# -_-.net
KiCad netlist of a schematic drawn in Altium Designer
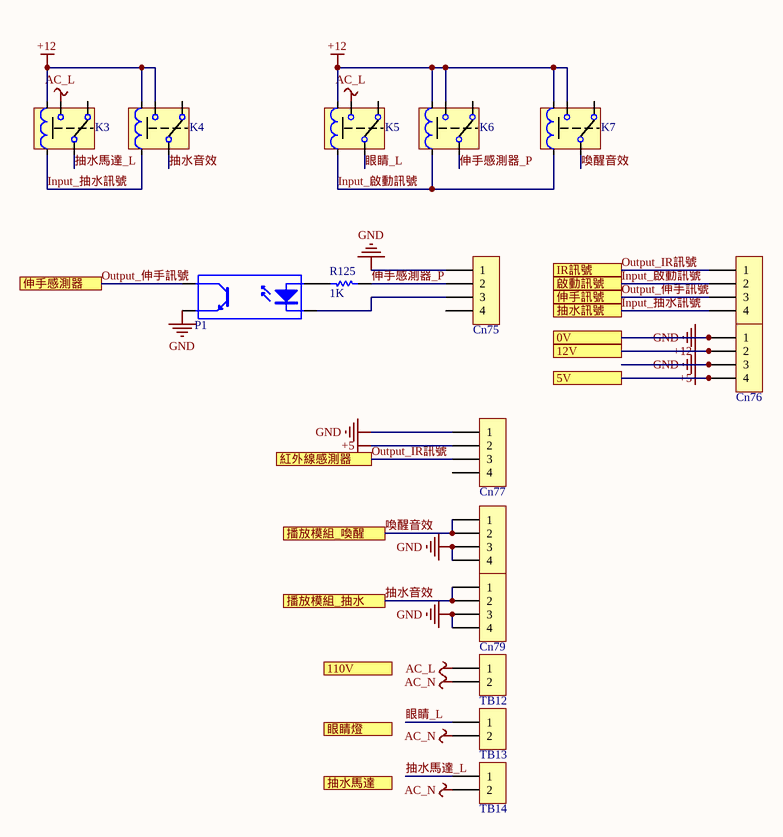
[diagram p0: 行天宮-流亡暗道-石像.SchDoc]

(export (version "E")
  (design (tool "Eeschema 10.0.6"))
  (components
    (comp (ref "Cn74")
      (value "KF2510-4")
      (footprint "Connector_KF2510-4W")
      (description "接線端子")
      (libsource (lib "MyLibray") (part "Contact(4P)"))
    )
    (comp (ref "Cn75")
      (value "KF2510-4")
      (footprint "Connector_KF2510-4W")
      (description "接線端子")
      (libsource (lib "MyLibray") (part "Contact(4P)"))
    )
    (comp (ref "Cn76")
      (value "KF2510-4")
      (footprint "Connector_KF2510-4W")
      (description "接線端子")
      (libsource (lib "MyLibray") (part "Contact(4P)"))
    )
    (comp (ref "Cn77")
      (value "KF2510-4")
      (footprint "Connector_KF2510-4W")
      (description "接線端子")
      (libsource (lib "MyLibray") (part "Contact(4P)"))
    )
    (comp (ref "Cn78")
      (value "KF2510-4")
      (footprint "Connector_KF2510-4W")
      (description "接線端子")
      (libsource (lib "MyLibray") (part "Contact(4P)"))
    )
    (comp (ref "Cn79")
      (value "KF2510-4")
      (footprint "Connector_KF2510-4W")
      (description "接線端子")
      (libsource (lib "MyLibray") (part "Contact(4P)"))
    )
    (comp (ref "K3")
      (value "G2R-1-24VDC")
      (footprint "RELAY-HF41F-012-ZST")
      (description "繼電器")
      (libsource (lib "MyLibray") (part "Relay"))
    )
    (comp (ref "K4")
      (value "G2R-1-24VDC")
      (footprint "RELAY-HF41F-012-ZST")
      (description "繼電器")
      (libsource (lib "MyLibray") (part "Relay"))
    )
    (comp (ref "K5")
      (value "G2R-1-24VDC")
      (footprint "RELAY-HF41F-012-ZST")
      (description "繼電器")
      (libsource (lib "MyLibray") (part "Relay"))
    )
    (comp (ref "K6")
      (value "G2R-1-24VDC")
      (footprint "RELAY-HF41F-012-ZST")
      (description "繼電器")
      (libsource (lib "MyLibray") (part "Relay"))
    )
    (comp (ref "K7")
      (value "G2R-1-24VDC")
      (footprint "RELAY-HF41F-012-ZST")
      (description "繼電器")
      (libsource (lib "MyLibray") (part "Relay"))
    )
    (comp (ref "P1")
      (value "PC817")
      (footprint "PC817")
      (description "光耦")
      (libsource (lib "MyLibray") (part "PC817"))
    )
    (comp (ref "R125")
      (value "1K")
      (footprint "Res_1/4")
      (description "電阻")
      (libsource (lib "MyLibray") (part "Res"))
    )
    (comp (ref "TB12")
      (value "ZB25(2P)")
      (footprint "Terminal block(KF2EDGR-5.08 _2P)")
      (description "端子台")
      (libsource (lib "MyLibray") (part "Terminal block(2P)"))
    )
    (comp (ref "TB13")
      (value "ZB25(2P)")
      (footprint "Terminal block(KF2EDGR-5.08 _2P)")
      (description "端子台")
      (libsource (lib "MyLibray") (part "Terminal block(2P)"))
    )
    (comp (ref "TB14")
      (value "ZB25(2P)")
      (footprint "Terminal block(KF2EDGR-5.08 _2P)")
      (description "端子台")
      (libsource (lib "MyLibray") (part "Terminal block(2P)"))
    )
  )
  (nets
    (net (code "1") (name "+5") (class "Default")
      (node (ref "Cn76") (pin "4") (pinfunction "4_4") (pintype "passive"))
      (node (ref "Cn77") (pin "2") (pinfunction "2_2") (pintype "passive"))
    )
    (net (code "2") (name "+12") (class "Default")
      (node (ref "Cn76") (pin "2") (pinfunction "2_2") (pintype "passive"))
      (node (ref "K3") (pin "5") (pinfunction "A2_5") (pintype "passive"))
      (node (ref "K4") (pin "2") (pinfunction "NO_2") (pintype "passive"))
      (node (ref "K4") (pin "5") (pinfunction "A2_5") (pintype "passive"))
      (node (ref "K5") (pin "5") (pinfunction "A2_5") (pintype "passive"))
      (node (ref "K6") (pin "2") (pinfunction "NO_2") (pintype "passive"))
      (node (ref "K6") (pin "5") (pinfunction "A2_5") (pintype "passive"))
      (node (ref "K7") (pin "2") (pinfunction "NO_2") (pintype "passive"))
      (node (ref "K7") (pin "5") (pinfunction "A2_5") (pintype "passive"))
    )
    (net (code "4") (name "/Input_啟動訊號") (class "Default")
      (node (ref "Cn74") (pin "2") (pinfunction "2_2") (pintype "passive"))
      (node (ref "K5") (pin "4") (pinfunction "A1_4") (pintype "passive"))
      (node (ref "K6") (pin "4") (pinfunction "A1_4") (pintype "passive"))
      (node (ref "K7") (pin "4") (pinfunction "A1_4") (pintype "passive"))
    )
    (net (code "5") (name "/Input_抽水訊號") (class "Default")
      (node (ref "Cn74") (pin "4") (pinfunction "4_4") (pintype "passive"))
      (node (ref "K3") (pin "4") (pinfunction "A1_4") (pintype "passive"))
      (node (ref "K4") (pin "4") (pinfunction "A1_4") (pintype "passive"))
    )
    (net (code "6") (name "/Output_IR訊號") (class "Default")
      (node (ref "Cn74") (pin "1") (pinfunction "1_1") (pintype "passive"))
      (node (ref "Cn77") (pin "3") (pinfunction "3_3") (pintype "passive"))
    )
    (net (code "7") (name "/Output_伸手訊號") (class "Default")
      (node (ref "Cn74") (pin "3") (pinfunction "3_3") (pintype "passive"))
      (node (ref "P1") (pin "4") (pinfunction "C_4") (pintype "passive"))
    )
    (net (code "8") (name "/伸手感測器_P") (class "Default")
      (node (ref "Cn75") (pin "2") (pinfunction "2_2") (pintype "passive"))
      (node (ref "K6") (pin "1") (pinfunction "COM_1") (pintype "passive"))
      (node (ref "R125") (pin "2") (pinfunction "2_2") (pintype "passive"))
    )
    (net (code "9") (name "/喚醒音效") (class "Default")
      (node (ref "Cn78") (pin "1") (pinfunction "1_1") (pintype "passive"))
      (node (ref "Cn78") (pin "2") (pinfunction "2_2") (pintype "passive"))
      (node (ref "K7") (pin "1") (pinfunction "COM_1") (pintype "passive"))
    )
    (net (code "10") (name "/抽水音效") (class "Default")
      (node (ref "Cn79") (pin "1") (pinfunction "1_1") (pintype "passive"))
      (node (ref "Cn79") (pin "2") (pinfunction "2_2") (pintype "passive"))
      (node (ref "K4") (pin "1") (pinfunction "COM_1") (pintype "passive"))
    )
    (net (code "12") (name "/抽水馬達_L") (class "Default")
      (node (ref "K3") (pin "1") (pinfunction "COM_1") (pintype "passive"))
      (node (ref "TB14") (pin "1") (pinfunction "1_1") (pintype "passive"))
    )
    (net (code "13") (name "/眼睛_L") (class "Default")
      (node (ref "K5") (pin "1") (pinfunction "COM_1") (pintype "passive"))
      (node (ref "TB13") (pin "1") (pinfunction "1_1") (pintype "passive"))
    )
    (net (code "15") (name "AC_L") (class "Default")
      (node (ref "K3") (pin "2") (pinfunction "NO_2") (pintype "passive"))
      (node (ref "K5") (pin "2") (pinfunction "NO_2") (pintype "passive"))
      (node (ref "TB12") (pin "1") (pinfunction "1_1") (pintype "passive"))
    )
    (net (code "16") (name "AC_N") (class "Default")
      (node (ref "TB12") (pin "2") (pinfunction "2_2") (pintype "passive"))
      (node (ref "TB13") (pin "2") (pinfunction "2_2") (pintype "passive"))
      (node (ref "TB14") (pin "2") (pinfunction "2_2") (pintype "passive"))
    )
    (net (code "17") (name "GND") (class "Default")
      (node (ref "Cn75") (pin "1") (pinfunction "1_1") (pintype "passive"))
      (node (ref "Cn76") (pin "1") (pinfunction "1_1") (pintype "passive"))
      (node (ref "Cn76") (pin "3") (pinfunction "3_3") (pintype "passive"))
      (node (ref "Cn77") (pin "1") (pinfunction "1_1") (pintype "passive"))
      (node (ref "Cn78") (pin "3") (pinfunction "3_3") (pintype "passive"))
      (node (ref "Cn78") (pin "4") (pinfunction "4_4") (pintype "passive"))
      (node (ref "Cn79") (pin "3") (pinfunction "3_3") (pintype "passive"))
      (node (ref "Cn79") (pin "4") (pinfunction "4_4") (pintype "passive"))
      (node (ref "P1") (pin "3") (pinfunction "E_3") (pintype "passive"))
    )
    (net (code "18") (name "Net-(P1-A)") (class "Default")
      (node (ref "P1") (pin "1") (pinfunction "A_1") (pintype "passive"))
      (node (ref "R125") (pin "1") (pinfunction "1_1") (pintype "passive"))
    )
    (net (code "19") (name "Net-(P1-K)") (class "Default")
      (node (ref "Cn75") (pin "3") (pinfunction "3_3") (pintype "passive"))
      (node (ref "P1") (pin "2") (pinfunction "K_2") (pintype "passive"))
    )
    (net (code "20") (name "unconnected-(Cn75-Pad4)") (class "Default")
      (node (ref "Cn75") (pin "4") (pinfunction "4_4") (pintype "passive"))
    )
    (net (code "21") (name "unconnected-(Cn77-Pad4)") (class "Default")
      (node (ref "Cn77") (pin "4") (pinfunction "4_4") (pintype "passive"))
    )
    (net (code "22") (name "unconnected-(K3-NC-Pad3)") (class "Default")
      (node (ref "K3") (pin "3") (pinfunction "NC_3") (pintype "passive"))
    )
    (net (code "23") (name "unconnected-(K4-NC-Pad3)") (class "Default")
      (node (ref "K4") (pin "3") (pinfunction "NC_3") (pintype "passive"))
    )
    (net (code "24") (name "unconnected-(K5-NC-Pad3)") (class "Default")
      (node (ref "K5") (pin "3") (pinfunction "NC_3") (pintype "passive"))
    )
    (net (code "25") (name "unconnected-(K6-NC-Pad3)") (class "Default")
      (node (ref "K6") (pin "3") (pinfunction "NC_3") (pintype "passive"))
    )
    (net (code "26") (name "unconnected-(K7-NC-Pad3)") (class "Default")
      (node (ref "K7") (pin "3") (pinfunction "NC_3") (pintype "passive"))
    )
  )
)
